# Tube_board_v3.net
KiCad netlist of a schematic drawn in EAGLE
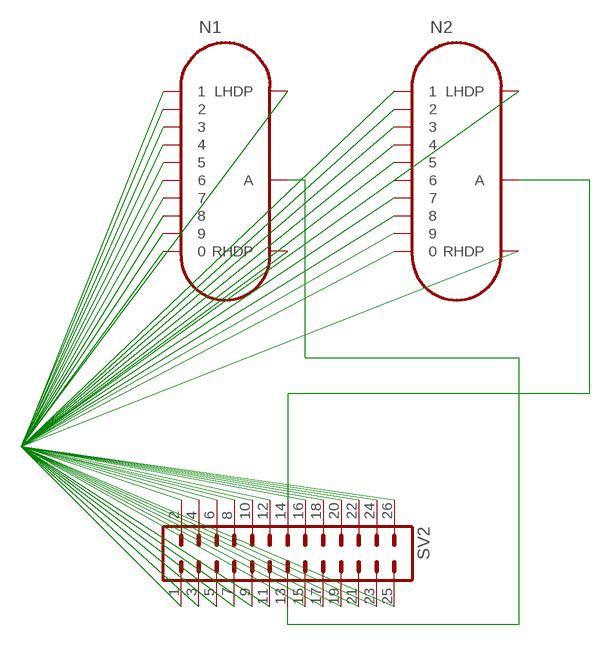
[diagram p0: schematic, sheet 1]

(export (version "E")
  (design (tool "Eeschema 10.0.6"))
  (components
    (comp (ref "N1")
      (value "IN-14")
      (footprint "eagle-import:IN-14")
      (libsource (lib "eagle-import") (part "IN-14"))
    )
    (comp (ref "N2")
      (value "IN-14")
      (footprint "eagle-import:IN-14")
      (libsource (lib "eagle-import") (part "IN-14"))
    )
    (comp (ref "SV2")
      (value "MA13-2")
      (footprint "eagle-import:MA13-2")
      (libsource (lib "eagle-import") (part "MA13-2"))
    )
  )
  (nets
    (net (code "1") (name "Net-(N1-Pad0)") (class "Default")
      (node (ref "N1") (pin "0") (pinfunction "0_0") (pintype "bidirectional"))
      (node (ref "N1") (pin "1") (pinfunction "1_1") (pintype "bidirectional"))
      (node (ref "N1") (pin "2") (pinfunction "2_2") (pintype "bidirectional"))
      (node (ref "N1") (pin "3") (pinfunction "3_3") (pintype "bidirectional"))
      (node (ref "N1") (pin "4") (pinfunction "4_4") (pintype "bidirectional"))
      (node (ref "N1") (pin "5") (pinfunction "5_5") (pintype "bidirectional"))
      (node (ref "N1") (pin "6") (pinfunction "6_6") (pintype "bidirectional"))
      (node (ref "N1") (pin "7") (pinfunction "7_7") (pintype "bidirectional"))
      (node (ref "N1") (pin "8") (pinfunction "8_8") (pintype "bidirectional"))
      (node (ref "N1") (pin "9") (pinfunction "9_9") (pintype "bidirectional"))
      (node (ref "N1") (pin "LHDP") (pinfunction "LHDP_LHDP") (pintype "bidirectional"))
      (node (ref "N1") (pin "RHDP") (pinfunction "RHDP_RHDP") (pintype "bidirectional"))
      (node (ref "N2") (pin "0") (pinfunction "0_0") (pintype "bidirectional"))
      (node (ref "N2") (pin "1") (pinfunction "1_1") (pintype "bidirectional"))
      (node (ref "N2") (pin "2") (pinfunction "2_2") (pintype "bidirectional"))
      (node (ref "N2") (pin "3") (pinfunction "3_3") (pintype "bidirectional"))
      (node (ref "N2") (pin "4") (pinfunction "4_4") (pintype "bidirectional"))
      (node (ref "N2") (pin "5") (pinfunction "5_5") (pintype "bidirectional"))
      (node (ref "N2") (pin "6") (pinfunction "6_6") (pintype "bidirectional"))
      (node (ref "N2") (pin "7") (pinfunction "7_7") (pintype "bidirectional"))
      (node (ref "N2") (pin "8") (pinfunction "8_8") (pintype "bidirectional"))
      (node (ref "N2") (pin "9") (pinfunction "9_9") (pintype "bidirectional"))
      (node (ref "N2") (pin "LHDP") (pinfunction "LHDP_LHDP") (pintype "bidirectional"))
      (node (ref "N2") (pin "RHDP") (pinfunction "RHDP_RHDP") (pintype "bidirectional"))
      (node (ref "SV2") (pin "1") (pinfunction "1_1") (pintype "passive"))
      (node (ref "SV2") (pin "10") (pinfunction "10_10") (pintype "passive"))
      (node (ref "SV2") (pin "11") (pinfunction "11_11") (pintype "passive"))
      (node (ref "SV2") (pin "12") (pinfunction "12_12") (pintype "passive"))
      (node (ref "SV2") (pin "15") (pinfunction "15_15") (pintype "passive"))
      (node (ref "SV2") (pin "16") (pinfunction "16_16") (pintype "passive"))
      (node (ref "SV2") (pin "17") (pinfunction "17_17") (pintype "passive"))
      (node (ref "SV2") (pin "18") (pinfunction "18_18") (pintype "passive"))
      (node (ref "SV2") (pin "19") (pinfunction "19_19") (pintype "passive"))
      (node (ref "SV2") (pin "2") (pinfunction "2_2") (pintype "passive"))
      (node (ref "SV2") (pin "20") (pinfunction "20_20") (pintype "passive"))
      (node (ref "SV2") (pin "21") (pinfunction "21_21") (pintype "passive"))
      (node (ref "SV2") (pin "22") (pinfunction "22_22") (pintype "passive"))
      (node (ref "SV2") (pin "23") (pinfunction "23_23") (pintype "passive"))
      (node (ref "SV2") (pin "24") (pinfunction "24_24") (pintype "passive"))
      (node (ref "SV2") (pin "25") (pinfunction "25_25") (pintype "passive"))
      (node (ref "SV2") (pin "26") (pinfunction "26_26") (pintype "passive"))
      (node (ref "SV2") (pin "3") (pinfunction "3_3") (pintype "passive"))
      (node (ref "SV2") (pin "4") (pinfunction "4_4") (pintype "passive"))
      (node (ref "SV2") (pin "5") (pinfunction "5_5") (pintype "passive"))
      (node (ref "SV2") (pin "6") (pinfunction "6_6") (pintype "passive"))
      (node (ref "SV2") (pin "7") (pinfunction "7_7") (pintype "passive"))
      (node (ref "SV2") (pin "8") (pinfunction "8_8") (pintype "passive"))
      (node (ref "SV2") (pin "9") (pinfunction "9_9") (pintype "passive"))
    )
    (net (code "2") (name "Net-(N1-PadA)") (class "Default")
      (node (ref "N1") (pin "A") (pinfunction "A_A") (pintype "bidirectional"))
      (node (ref "SV2") (pin "13") (pinfunction "13_13") (pintype "passive"))
    )
    (net (code "3") (name "Net-(N2-PadA)") (class "Default")
      (node (ref "N2") (pin "A") (pinfunction "A_A") (pintype "bidirectional"))
      (node (ref "SV2") (pin "14") (pinfunction "14_14") (pintype "passive"))
    )
  )
)
